# PCB_Project_Board_2.net
KiCad netlist of a schematic drawn in Altium Designer
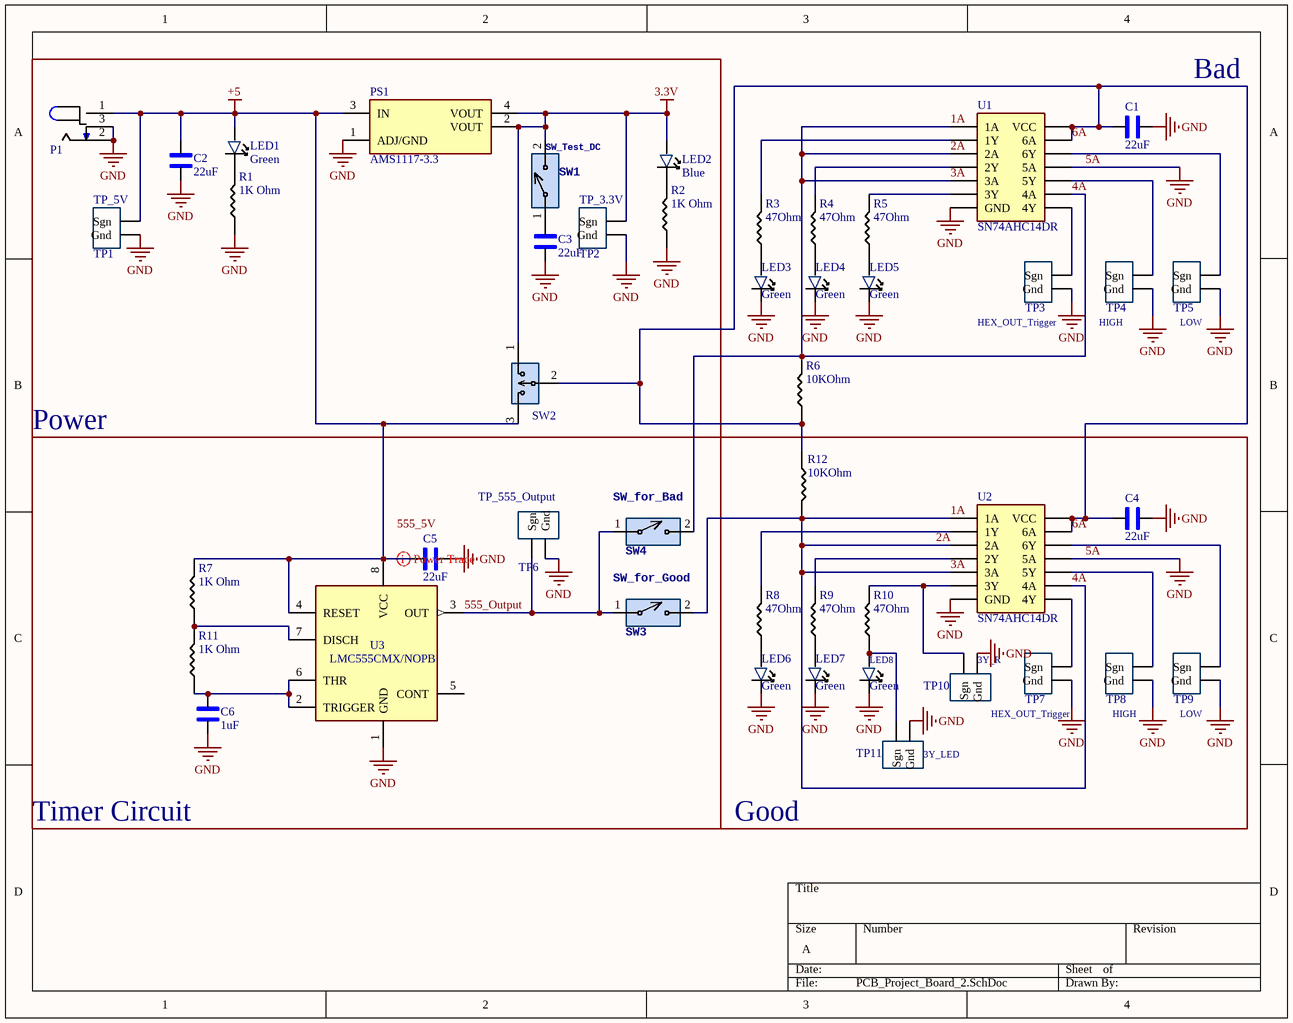
[diagram p0: PCB_Project_Board_2.SchDoc]

(export (version "E")
  (design (tool "Eeschema 10.0.6"))
  (components
    (comp (ref "C1")
      (value "22uF")
      (footprint "1206_Passive_Capacitor")
      (description "22uF ±10% 25V X5R 1206 Multilayer Ceramic Capacitors MLCC - SMD/SMT RoHS")
      (fields (field (name "MFR PART #") "CL31A226KAHNNNE") (field (name "LCSC PART#") "C12891"))
      (libsource (lib "ECEN5730Lib_2023_01_DS") (part "C_22uF_1206"))
    )
    (comp (ref "C2")
      (value "22uF")
      (footprint "1206_Passive_Capacitor")
      (description "22uF ±10% 25V X5R 1206 Multilayer Ceramic Capacitors MLCC - SMD/SMT RoHS")
      (fields (field (name "MFR PART #") "CL31A226KAHNNNE") (field (name "LCSC PART#") "C12891"))
      (libsource (lib "ECEN5730Lib_2023_01_DS") (part "C_22uF_1206"))
    )
    (comp (ref "C3")
      (value "22uF")
      (footprint "1206_Passive_Capacitor")
      (description "22uF ±10% 25V X5R 1206 Multilayer Ceramic Capacitors MLCC - SMD/SMT RoHS")
      (fields (field (name "MFR PART #") "CL31A226KAHNNNE") (field (name "LCSC PART#") "C12891"))
      (libsource (lib "ECEN5730Lib_2023_01_DS") (part "C_22uF_1206"))
    )
    (comp (ref "C4")
      (value "22uF")
      (footprint "1206_Passive_Capacitor")
      (description "22uF ±10% 25V X5R 1206 Multilayer Ceramic Capacitors MLCC - SMD/SMT RoHS")
      (fields (field (name "MFR PART #") "CL31A226KAHNNNE") (field (name "LCSC PART#") "C12891"))
      (libsource (lib "ECEN5730Lib_2023_01_DS") (part "C_22uF_1206"))
    )
    (comp (ref "C5")
      (value "22uF")
      (footprint "1206_Passive_Capacitor")
      (description "22uF ±10% 25V X5R 1206 Multilayer Ceramic Capacitors MLCC - SMD/SMT RoHS")
      (fields (field (name "MFR PART #") "CL31A226KAHNNNE") (field (name "LCSC PART#") "C12891"))
      (libsource (lib "ECEN5730Lib_2023_01_DS") (part "C_22uF_1206"))
    )
    (comp (ref "C6")
      (value "1uF")
      (footprint "1206_Passive_Capacitor")
      (description "MULTILAYER CERAMIC CAPACITORS MLCC - SMD/SMT 1UF 50V 1206 ROHS")
      (fields (field (name "MFR PART #") "CL31B105KBHNNNE") (field (name "LCSC PART#") "C1848"))
      (libsource (lib "ECEN5730Lib_2023_01_DS") (part "C_1uF_1206"))
    )
    (comp (ref "LED1")
      (value "Green")
      (footprint "LED_1206")
      (description "Green 513~528nm 1206 Light Emitting Diodes (LED) RoHS")
      (fields (field (name "MFR PART #") "SZYY1206G") (field (name "LCSC PART#") "C434439"))
      (libsource (lib "ECEN5730Lib_2023_01_DS") (part "LED_GREEN_1206"))
    )
    (comp (ref "LED2")
      (value "Blue")
      (footprint "LED_1206")
      (description "blue 1206  Light Emitting Diodes (LED) ROHS")
      (fields (field (name "MFR PART #") "NCD1206B1") (field (name "LCSC PART#") "C130717"))
      (libsource (lib "ECEN5730Lib_2023_01_DS") (part "LED_BLUE_1206"))
    )
    (comp (ref "LED3")
      (value "Green")
      (footprint "LED_1206")
      (description "Green 513~528nm 1206 Light Emitting Diodes (LED) RoHS")
      (fields (field (name "MFR PART #") "SZYY1206G") (field (name "LCSC PART#") "C434439"))
      (libsource (lib "ECEN5730Lib_2023_01_DS") (part "LED_GREEN_1206"))
    )
    (comp (ref "LED4")
      (value "Green")
      (footprint "LED_1206")
      (description "Green 513~528nm 1206 Light Emitting Diodes (LED) RoHS")
      (fields (field (name "MFR PART #") "SZYY1206G") (field (name "LCSC PART#") "C434439"))
      (libsource (lib "ECEN5730Lib_2023_01_DS") (part "LED_GREEN_1206"))
    )
    (comp (ref "LED5")
      (value "Green")
      (footprint "LED_1206")
      (description "Green 513~528nm 1206 Light Emitting Diodes (LED) RoHS")
      (fields (field (name "MFR PART #") "SZYY1206G") (field (name "LCSC PART#") "C434439"))
      (libsource (lib "ECEN5730Lib_2023_01_DS") (part "LED_GREEN_1206"))
    )
    (comp (ref "LED6")
      (value "Green")
      (footprint "LED_1206")
      (description "Green 513~528nm 1206 Light Emitting Diodes (LED) RoHS")
      (fields (field (name "MFR PART #") "SZYY1206G") (field (name "LCSC PART#") "C434439"))
      (libsource (lib "ECEN5730Lib_2023_01_DS") (part "LED_GREEN_1206"))
    )
    (comp (ref "LED7")
      (value "Green")
      (footprint "LED_1206")
      (description "Green 513~528nm 1206 Light Emitting Diodes (LED) RoHS")
      (fields (field (name "MFR PART #") "SZYY1206G") (field (name "LCSC PART#") "C434439"))
      (libsource (lib "ECEN5730Lib_2023_01_DS") (part "LED_GREEN_1206"))
    )
    (comp (ref "LED8")
      (value "Green")
      (footprint "LED_1206")
      (description "Green 513~528nm 1206 Light Emitting Diodes (LED) RoHS")
      (fields (field (name "MFR PART #") "SZYY1206G") (field (name "LCSC PART#") "C434439"))
      (libsource (lib "ECEN5730Lib_2023_01_DS") (part "LED_GREEN_1206"))
    )
    (comp (ref "P1")
      (value "Power Jack")
      (footprint "Power_Jack")
      (description "Power Barrel Connector Jack 2.10mm ID (0.083\"), 5.50mm OD (0.217\") Through Hole, Right Angle")
      (fields (field (name "MFR PART #") "PJ-102A") (field (name "LCSC PART#") "C136744"))
      (libsource (lib "ECEN5730Lib_2023_01_DS") (part "P_Power Jack"))
    )
    (comp (ref "PS1")
      (value "AMS1117-3.3")
      (footprint "LDO")
      (description "LOW DROPOUT REGULATORS(LDO) POSITIVE FIXED 1.3V @ 800MA 15V 3.3V 1A SOT-223 ROHS")
      (fields (field (name "LCSC PART#") "C6186"))
      (libsource (lib "ECEN5730Lib_2023_01_DS") (part "PS_AMS_LDO_3v3"))
    )
    (comp (ref "R1")
      (value "1K Ohm")
      (footprint "1206_Passive_Resitor")
      (description "CHIP RESISTOR - SURFACE MOUNT 1KOHMS ±1% 1/4W 1206 ROHS")
      (fields (field (name "MFR PART #") "RNCP1206FTD1K00CT") (field (name "LCSC PART#") "C4410"))
      (libsource (lib "ECEN5730Lib_2023_01_DS") (part "R_1K_1206"))
    )
    (comp (ref "R2")
      (value "1K Ohm")
      (footprint "1206_Passive_Resitor")
      (description "CHIP RESISTOR - SURFACE MOUNT 1KOHMS ±1% 1/4W 1206 ROHS")
      (fields (field (name "MFR PART #") "RNCP1206FTD1K00CT") (field (name "LCSC PART#") "C4410"))
      (libsource (lib "ECEN5730Lib_2023_01_DS") (part "R_1K_1206"))
    )
    (comp (ref "R3")
      (value "47Ohm")
      (footprint "1206_Passive_Resitor")
      (description "47Ω ±5% 0.25W ±200ppm/℃ 1206 Chip Resistor - Surface Mount RoHS")
      (fields (field (name "MFR PART #") "1206W4J0470T5E") (field (name "LCSC PART#") "C25384"))
      (libsource (lib "ECEN5730Lib_2023_01_DS") (part "R_47Ohm_1206"))
    )
    (comp (ref "R4")
      (value "47Ohm")
      (footprint "1206_Passive_Resitor")
      (description "47Ω ±5% 0.25W ±200ppm/℃ 1206 Chip Resistor - Surface Mount RoHS")
      (fields (field (name "MFR PART #") "1206W4J0470T5E") (field (name "LCSC PART#") "C25384"))
      (libsource (lib "ECEN5730Lib_2023_01_DS") (part "R_47Ohm_1206"))
    )
    (comp (ref "R5")
      (value "47Ohm")
      (footprint "1206_Passive_Resitor")
      (description "47Ω ±5% 0.25W ±200ppm/℃ 1206 Chip Resistor - Surface Mount RoHS")
      (fields (field (name "MFR PART #") "1206W4J0470T5E") (field (name "LCSC PART#") "C25384"))
      (libsource (lib "ECEN5730Lib_2023_01_DS") (part "R_47Ohm_1206"))
    )
    (comp (ref "R6")
      (value "10KOhm")
      (footprint "1206_Passive_Resitor")
      (description "10 kOhms ±5% 0.25W, 1/4W Chip Resistor 1206 (3216 Metric) Automotive AEC-Q200 Thick Film")
      (fields (field (name "MFR PART #") "RMCF1206FT10K0") (field (name "LCSC PART#") "C17902"))
      (libsource (lib "ECEN5730Lib_2023_01_DS") (part "R_10KOhm_1206"))
    )
    (comp (ref "R7")
      (value "1K Ohm")
      (footprint "1206_Passive_Resitor")
      (description "CHIP RESISTOR - SURFACE MOUNT 1KOHMS ±1% 1/4W 1206 ROHS")
      (fields (field (name "MFR PART #") "RNCP1206FTD1K00CT") (field (name "LCSC PART#") "C4410"))
      (libsource (lib "ECEN5730Lib_2023_01_DS") (part "R_1K_1206"))
    )
    (comp (ref "R8")
      (value "47Ohm")
      (footprint "1206_Passive_Resitor")
      (description "47Ω ±5% 0.25W ±200ppm/℃ 1206 Chip Resistor - Surface Mount RoHS")
      (fields (field (name "MFR PART #") "1206W4J0470T5E") (field (name "LCSC PART#") "C25384"))
      (libsource (lib "ECEN5730Lib_2023_01_DS") (part "R_47Ohm_1206"))
    )
    (comp (ref "R9")
      (value "47Ohm")
      (footprint "1206_Passive_Resitor")
      (description "47Ω ±5% 0.25W ±200ppm/℃ 1206 Chip Resistor - Surface Mount RoHS")
      (fields (field (name "MFR PART #") "1206W4J0470T5E") (field (name "LCSC PART#") "C25384"))
      (libsource (lib "ECEN5730Lib_2023_01_DS") (part "R_47Ohm_1206"))
    )
    (comp (ref "R10")
      (value "47Ohm")
      (footprint "1206_Passive_Resitor")
      (description "47Ω ±5% 0.25W ±200ppm/℃ 1206 Chip Resistor - Surface Mount RoHS")
      (fields (field (name "MFR PART #") "1206W4J0470T5E") (field (name "LCSC PART#") "C25384"))
      (libsource (lib "ECEN5730Lib_2023_01_DS") (part "R_47Ohm_1206"))
    )
    (comp (ref "R11")
      (value "1K Ohm")
      (footprint "1206_Passive_Resitor")
      (description "CHIP RESISTOR - SURFACE MOUNT 1KOHMS ±1% 1/4W 1206 ROHS")
      (fields (field (name "MFR PART #") "RNCP1206FTD1K00CT") (field (name "LCSC PART#") "C4410"))
      (libsource (lib "ECEN5730Lib_2023_01_DS") (part "R_1K_1206"))
    )
    (comp (ref "R12")
      (value "10KOhm")
      (footprint "1206_Passive_Resitor")
      (description "10 kOhms ±5% 0.25W, 1/4W Chip Resistor 1206 (3216 Metric) Automotive AEC-Q200 Thick Film")
      (fields (field (name "MFR PART #") "RMCF1206FT10K0") (field (name "LCSC PART#") "C17902"))
      (libsource (lib "ECEN5730Lib_2023_01_DS") (part "R_10KOhm_1206"))
    )
    (comp (ref "SW1")
      (value "SW_Test_DC")
      (footprint "2Pin-Header-Conn")
      (description "2Pin Header")
      (fields (field (name "LCSC PART#") "C124375"))
      (libsource (lib "") (part "SW_2Pin_100mil_Switch_1"))
    )
    (comp (ref "SW2")
      (value "PREC003SAAN-RC")
      (footprint "3_PIN_100mil")
      (description "Connector Header Through Hole 3 position 0.100\" (2.54mm)")
      (fields (field (name "LCSC PART#") "C49257"))
      (libsource (lib "ECEN5730Lib_2023_01_DS") (part "SW_3Pin_100mil_Switch"))
    )
    (comp (ref "SW3")
      (value "SW_for_Good")
      (footprint "2Pin-Header-Conn")
      (description "2Pin Header")
      (fields (field (name "LCSC PART#") "C124375"))
      (libsource (lib "ECEN5730Lib_2023_01_DS") (part "SW_2Pin_100mil_Switch"))
    )
    (comp (ref "SW4")
      (value "SW_for_Bad")
      (footprint "2Pin-Header-Conn")
      (description "2Pin Header")
      (fields (field (name "LCSC PART#") "C124375"))
      (libsource (lib "ECEN5730Lib_2023_01_DS") (part "SW_2Pin_100mil_Switch"))
    )
    (comp (ref "TP1")
      (value "TP_5V")
      (footprint "TP10x_Probe")
      (description "Test Point 300 mil centers")
      (libsource (lib "ECEN5730Lib_2023_01_DS") (part "TP_10x_Probe"))
    )
    (comp (ref "TP2")
      (value "TP_3.3V")
      (footprint "TP10x_Probe")
      (description "Test Point 300 mil centers")
      (libsource (lib "ECEN5730Lib_2023_01_DS") (part "TP_10x_Probe"))
    )
    (comp (ref "TP3")
      (value "HEX_OUT_Trigger")
      (footprint "TP10x_Probe")
      (description "Test Point 300 mil centers")
      (libsource (lib "ECEN5730Lib_2023_01_DS") (part "TP_10x_Probe"))
    )
    (comp (ref "TP4")
      (value "HIGH")
      (footprint "TP10x_Probe")
      (description "Test Point 300 mil centers")
      (libsource (lib "ECEN5730Lib_2023_01_DS") (part "TP_10x_Probe"))
    )
    (comp (ref "TP5")
      (value "LOW")
      (footprint "TP10x_Probe")
      (description "Test Point 300 mil centers")
      (libsource (lib "ECEN5730Lib_2023_01_DS") (part "TP_10x_Probe"))
    )
    (comp (ref "TP6")
      (value "TP_555_Output")
      (footprint "TP10x_Probe")
      (description "Test Point 300 mil centers")
      (libsource (lib "") (part "TP_10x_Probe_2"))
    )
    (comp (ref "TP7")
      (value "HEX_OUT_Trigger")
      (footprint "TP10x_Probe")
      (description "Test Point 300 mil centers")
      (libsource (lib "ECEN5730Lib_2023_01_DS") (part "TP_10x_Probe"))
    )
    (comp (ref "TP8")
      (value "HIGH")
      (footprint "TP10x_Probe")
      (description "Test Point 300 mil centers")
      (libsource (lib "ECEN5730Lib_2023_01_DS") (part "TP_10x_Probe"))
    )
    (comp (ref "TP9")
      (value "LOW")
      (footprint "TP10x_Probe")
      (description "Test Point 300 mil centers")
      (libsource (lib "ECEN5730Lib_2023_01_DS") (part "TP_10x_Probe"))
    )
    (comp (ref "TP10")
      (value "3Y_R")
      (footprint "TP10x_Probe")
      (description "Test Point 300 mil centers")
      (libsource (lib "") (part "TP_10x_Probe_1"))
    )
    (comp (ref "TP11")
      (value "3Y_LED")
      (footprint "TP10x_Probe")
      (description "Test Point 300 mil centers")
      (libsource (lib "") (part "TP_10x_Probe_1"))
    )
    (comp (ref "U1")
      (value "SN74AHC14DR")
      (footprint "HEX_74AC14")
      (description "Inverter IC 6 Channel Schmitt Trigger 14-SOIC")
      (fields (field (name "LCSC PART#") "C6942"))
      (libsource (lib "ECEN5730Lib_2023_01_DS") (part "U_74_AHC_Hex"))
    )
    (comp (ref "U2")
      (value "SN74AHC14DR")
      (footprint "HEX_74AC14")
      (description "Inverter IC 6 Channel Schmitt Trigger 14-SOIC")
      (fields (field (name "LCSC PART#") "C6942"))
      (libsource (lib "ECEN5730Lib_2023_01_DS") (part "U_74_AHC_Hex"))
    )
    (comp (ref "U3")
      (value "LMC555CMX/NOPB")
      (footprint "TS555IDTTR")
      (description "555 Type, Timer/Oscillator _Single_ IC 3MHz 8-SO")
      (fields (field (name "LCSC PART#") "C90760"))
      (libsource (lib "ECEN5730Lib_2023_01_DS") (part "U_555_Fast"))
    )
  )
  (nets
    (net (code "1") (name "+5") (class "Default")
      (node (ref "C2") (pin "2") (pinfunction "2_2") (pintype "passive"))
      (node (ref "C5") (pin "2") (pinfunction "2_2") (pintype "passive"))
      (node (ref "LED1") (pin "1") (pinfunction "1_1") (pintype "passive"))
      (node (ref "P1") (pin "1") (pinfunction "1_1") (pintype "power_in"))
      (node (ref "PS1") (pin "3") (pinfunction "IN_3") (pintype "power_in"))
      (node (ref "R7") (pin "2") (pinfunction "2_2") (pintype "passive"))
      (node (ref "SW2") (pin "3") (pinfunction "3_3") (pintype "passive"))
      (node (ref "TP1") (pin "1") (pinfunction "Sgn_1") (pintype "passive"))
      (node (ref "U3") (pin "4") (pinfunction "RESET_4") (pintype "passive"))
      (node (ref "U3") (pin "8") (pinfunction "VCC_8") (pintype "power_in"))
    )
    (net (code "2") (name "/1A") (class "Default")
      (node (ref "R12") (pin "2") (pinfunction "2_2") (pintype "passive"))
      (node (ref "R6") (pin "2") (pinfunction "2_2") (pintype "passive"))
      (node (ref "SW3") (pin "2") (pinfunction "2_2") (pintype "passive"))
      (node (ref "SW4") (pin "2") (pinfunction "2_2") (pintype "passive"))
      (node (ref "U1") (pin "1") (pinfunction "1A_1") (pintype "passive"))
      (node (ref "U1") (pin "3") (pinfunction "2A_3") (pintype "passive"))
      (node (ref "U1") (pin "5") (pinfunction "3A_5") (pintype "passive"))
      (node (ref "U1") (pin "9") (pinfunction "4A_9") (pintype "passive"))
      (node (ref "U2") (pin "1") (pinfunction "1A_1") (pintype "passive"))
      (node (ref "U2") (pin "3") (pinfunction "2A_3") (pintype "passive"))
      (node (ref "U2") (pin "5") (pinfunction "3A_5") (pintype "passive"))
      (node (ref "U2") (pin "9") (pinfunction "4A_9") (pintype "passive"))
    )
    (net (code "3") (name "/6A") (class "Default")
      (node (ref "C1") (pin "1") (pinfunction "1_1") (pintype "passive"))
      (node (ref "C4") (pin "1") (pinfunction "1_1") (pintype "passive"))
      (node (ref "R12") (pin "1") (pinfunction "1_1") (pintype "passive"))
      (node (ref "R6") (pin "1") (pinfunction "1_1") (pintype "passive"))
      (node (ref "SW2") (pin "2") (pinfunction "2_2") (pintype "passive"))
      (node (ref "U1") (pin "13") (pinfunction "6A_13") (pintype "passive"))
      (node (ref "U1") (pin "14") (pinfunction "VCC_14") (pintype "passive"))
      (node (ref "U2") (pin "13") (pinfunction "6A_13") (pintype "passive"))
      (node (ref "U2") (pin "14") (pinfunction "VCC_14") (pintype "passive"))
    )
    (net (code "5") (name "/555_Output") (class "Default")
      (node (ref "SW3") (pin "1") (pinfunction "1_1") (pintype "passive"))
      (node (ref "SW4") (pin "1") (pinfunction "1_1") (pintype "passive"))
      (node (ref "TP6") (pin "1") (pinfunction "Sgn_1") (pintype "passive"))
      (node (ref "U3") (pin "3") (pinfunction "OUT_3") (pintype "output"))
    )
    (net (code "6") (name "3.3V") (class "Default")
      (node (ref "LED2") (pin "1") (pinfunction "1_1") (pintype "passive"))
      (node (ref "PS1") (pin "2") (pinfunction "VOUT_2") (pintype "power_in"))
      (node (ref "PS1") (pin "4") (pinfunction "VOUT_4") (pintype "power_in"))
      (node (ref "SW1") (pin "2") (pinfunction "2_2") (pintype "passive"))
      (node (ref "SW2") (pin "1") (pinfunction "1_1") (pintype "passive"))
      (node (ref "TP2") (pin "1") (pinfunction "Sgn_1") (pintype "passive"))
    )
    (net (code "7") (name "GND") (class "Default")
      (node (ref "C1") (pin "2") (pinfunction "2_2") (pintype "passive"))
      (node (ref "C2") (pin "1") (pinfunction "1_1") (pintype "passive"))
      (node (ref "C3") (pin "1") (pinfunction "1_1") (pintype "passive"))
      (node (ref "C4") (pin "2") (pinfunction "2_2") (pintype "passive"))
      (node (ref "C5") (pin "1") (pinfunction "1_1") (pintype "passive"))
      (node (ref "C6") (pin "1") (pinfunction "1_1") (pintype "passive"))
      (node (ref "LED3") (pin "2") (pinfunction "2_2") (pintype "passive"))
      (node (ref "LED4") (pin "2") (pinfunction "2_2") (pintype "passive"))
      (node (ref "LED5") (pin "2") (pinfunction "2_2") (pintype "passive"))
      (node (ref "LED6") (pin "2") (pinfunction "2_2") (pintype "passive"))
      (node (ref "LED7") (pin "2") (pinfunction "2_2") (pintype "passive"))
      (node (ref "LED8") (pin "2") (pinfunction "2_2") (pintype "passive"))
      (node (ref "P1") (pin "2") (pinfunction "2_2") (pintype "power_in"))
      (node (ref "P1") (pin "3") (pinfunction "3_3") (pintype "power_in"))
      (node (ref "PS1") (pin "1") (pinfunction "ADJ/GND_1") (pintype "passive"))
      (node (ref "R1") (pin "1") (pinfunction "1_1") (pintype "passive"))
      (node (ref "R2") (pin "1") (pinfunction "1_1") (pintype "passive"))
      (node (ref "TP1") (pin "2") (pinfunction "Gnd_2") (pintype "passive"))
      (node (ref "TP10") (pin "2") (pinfunction "Gnd_2") (pintype "passive"))
      (node (ref "TP11") (pin "2") (pinfunction "Gnd_2") (pintype "passive"))
      (node (ref "TP2") (pin "2") (pinfunction "Gnd_2") (pintype "passive"))
      (node (ref "TP3") (pin "2") (pinfunction "Gnd_2") (pintype "passive"))
      (node (ref "TP4") (pin "2") (pinfunction "Gnd_2") (pintype "passive"))
      (node (ref "TP5") (pin "2") (pinfunction "Gnd_2") (pintype "passive"))
      (node (ref "TP6") (pin "2") (pinfunction "Gnd_2") (pintype "passive"))
      (node (ref "TP7") (pin "2") (pinfunction "Gnd_2") (pintype "passive"))
      (node (ref "TP8") (pin "2") (pinfunction "Gnd_2") (pintype "passive"))
      (node (ref "TP9") (pin "2") (pinfunction "Gnd_2") (pintype "passive"))
      (node (ref "U1") (pin "11") (pinfunction "5A_11") (pintype "passive"))
      (node (ref "U1") (pin "7") (pinfunction "GND_7") (pintype "passive"))
      (node (ref "U2") (pin "11") (pinfunction "5A_11") (pintype "passive"))
      (node (ref "U2") (pin "7") (pinfunction "GND_7") (pintype "passive"))
      (node (ref "U3") (pin "1") (pinfunction "GND_1") (pintype "power_in"))
    )
    (net (code "8") (name "Net-(C3-Pad2)") (class "Default")
      (node (ref "C3") (pin "2") (pinfunction "2_2") (pintype "passive"))
      (node (ref "SW1") (pin "1") (pinfunction "1_1") (pintype "passive"))
    )
    (net (code "9") (name "Net-(LED1-Pad2)") (class "Default")
      (node (ref "LED1") (pin "2") (pinfunction "2_2") (pintype "passive"))
      (node (ref "R1") (pin "2") (pinfunction "2_2") (pintype "passive"))
    )
    (net (code "10") (name "Net-(LED2-Pad2)") (class "Default")
      (node (ref "LED2") (pin "2") (pinfunction "2_2") (pintype "passive"))
      (node (ref "R2") (pin "2") (pinfunction "2_2") (pintype "passive"))
    )
    (net (code "11") (name "Net-(LED3-Pad1)") (class "Default")
      (node (ref "LED3") (pin "1") (pinfunction "1_1") (pintype "passive"))
      (node (ref "R3") (pin "1") (pinfunction "1_1") (pintype "passive"))
    )
    (net (code "12") (name "Net-(LED4-Pad1)") (class "Default")
      (node (ref "LED4") (pin "1") (pinfunction "1_1") (pintype "passive"))
      (node (ref "R4") (pin "1") (pinfunction "1_1") (pintype "passive"))
    )
    (net (code "13") (name "Net-(LED5-Pad1)") (class "Default")
      (node (ref "LED5") (pin "1") (pinfunction "1_1") (pintype "passive"))
      (node (ref "R5") (pin "1") (pinfunction "1_1") (pintype "passive"))
    )
    (net (code "14") (name "Net-(LED6-Pad1)") (class "Default")
      (node (ref "LED6") (pin "1") (pinfunction "1_1") (pintype "passive"))
      (node (ref "R8") (pin "1") (pinfunction "1_1") (pintype "passive"))
    )
    (net (code "15") (name "Net-(LED7-Pad1)") (class "Default")
      (node (ref "LED7") (pin "1") (pinfunction "1_1") (pintype "passive"))
      (node (ref "R9") (pin "1") (pinfunction "1_1") (pintype "passive"))
    )
    (net (code "16") (name "Net-(TP3-Sgn)") (class "Default")
      (node (ref "TP3") (pin "1") (pinfunction "Sgn_1") (pintype "passive"))
      (node (ref "U1") (pin "8") (pinfunction "4Y_8") (pintype "passive"))
    )
    (net (code "17") (name "Net-(TP4-Sgn)") (class "Default")
      (node (ref "TP4") (pin "1") (pinfunction "Sgn_1") (pintype "passive"))
      (node (ref "U1") (pin "10") (pinfunction "5Y_10") (pintype "passive"))
    )
    (net (code "18") (name "Net-(TP5-Sgn)") (class "Default")
      (node (ref "TP5") (pin "1") (pinfunction "Sgn_1") (pintype "passive"))
      (node (ref "U1") (pin "12") (pinfunction "6Y_12") (pintype "passive"))
    )
    (net (code "19") (name "Net-(TP7-Sgn)") (class "Default")
      (node (ref "TP7") (pin "1") (pinfunction "Sgn_1") (pintype "passive"))
      (node (ref "U2") (pin "8") (pinfunction "4Y_8") (pintype "passive"))
    )
    (net (code "20") (name "Net-(TP8-Sgn)") (class "Default")
      (node (ref "TP8") (pin "1") (pinfunction "Sgn_1") (pintype "passive"))
      (node (ref "U2") (pin "10") (pinfunction "5Y_10") (pintype "passive"))
    )
    (net (code "21") (name "Net-(TP9-Sgn)") (class "Default")
      (node (ref "TP9") (pin "1") (pinfunction "Sgn_1") (pintype "passive"))
      (node (ref "U2") (pin "12") (pinfunction "6Y_12") (pintype "passive"))
    )
    (net (code "22") (name "Net-(TP10-Sgn)") (class "Default")
      (node (ref "R10") (pin "2") (pinfunction "2_2") (pintype "passive"))
      (node (ref "TP10") (pin "1") (pinfunction "Sgn_1") (pintype "passive"))
      (node (ref "U2") (pin "6") (pinfunction "3Y_6") (pintype "passive"))
    )
    (net (code "23") (name "Net-(TP11-Sgn)") (class "Default")
      (node (ref "LED8") (pin "1") (pinfunction "1_1") (pintype "passive"))
      (node (ref "R10") (pin "1") (pinfunction "1_1") (pintype "passive"))
      (node (ref "TP11") (pin "1") (pinfunction "Sgn_1") (pintype "passive"))
    )
    (net (code "24") (name "Net-(U1-1Y)") (class "Default")
      (node (ref "R3") (pin "2") (pinfunction "2_2") (pintype "passive"))
      (node (ref "U1") (pin "2") (pinfunction "1Y_2") (pintype "passive"))
    )
    (net (code "25") (name "Net-(U1-2Y)") (class "Default")
      (node (ref "R4") (pin "2") (pinfunction "2_2") (pintype "passive"))
      (node (ref "U1") (pin "4") (pinfunction "2Y_4") (pintype "passive"))
    )
    (net (code "26") (name "Net-(U1-3Y)") (class "Default")
      (node (ref "R5") (pin "2") (pinfunction "2_2") (pintype "passive"))
      (node (ref "U1") (pin "6") (pinfunction "3Y_6") (pintype "passive"))
    )
    (net (code "27") (name "Net-(U2-1Y)") (class "Default")
      (node (ref "R8") (pin "2") (pinfunction "2_2") (pintype "passive"))
      (node (ref "U2") (pin "2") (pinfunction "1Y_2") (pintype "passive"))
    )
    (net (code "28") (name "Net-(U2-2Y)") (class "Default")
      (node (ref "R9") (pin "2") (pinfunction "2_2") (pintype "passive"))
      (node (ref "U2") (pin "4") (pinfunction "2Y_4") (pintype "passive"))
    )
    (net (code "29") (name "Net-(U3-DISCH)") (class "Default")
      (node (ref "R11") (pin "2") (pinfunction "2_2") (pintype "passive"))
      (node (ref "R7") (pin "1") (pinfunction "1_1") (pintype "passive"))
      (node (ref "U3") (pin "7") (pinfunction "DISCH_7") (pintype "passive"))
    )
    (net (code "30") (name "Net-(U3-THR)") (class "Default")
      (node (ref "C6") (pin "2") (pinfunction "2_2") (pintype "passive"))
      (node (ref "R11") (pin "1") (pinfunction "1_1") (pintype "passive"))
      (node (ref "U3") (pin "2") (pinfunction "TRIGGER_2") (pintype "passive"))
      (node (ref "U3") (pin "6") (pinfunction "THR_6") (pintype "passive"))
    )
    (net (code "31") (name "unconnected-(U3-CONT-Pad5)") (class "Default")
      (node (ref "U3") (pin "5") (pinfunction "CONT_5") (pintype "passive"))
    )
  )
)
